# G17_Sensor_V3.net
KiCad netlist of a schematic drawn in EAGLE
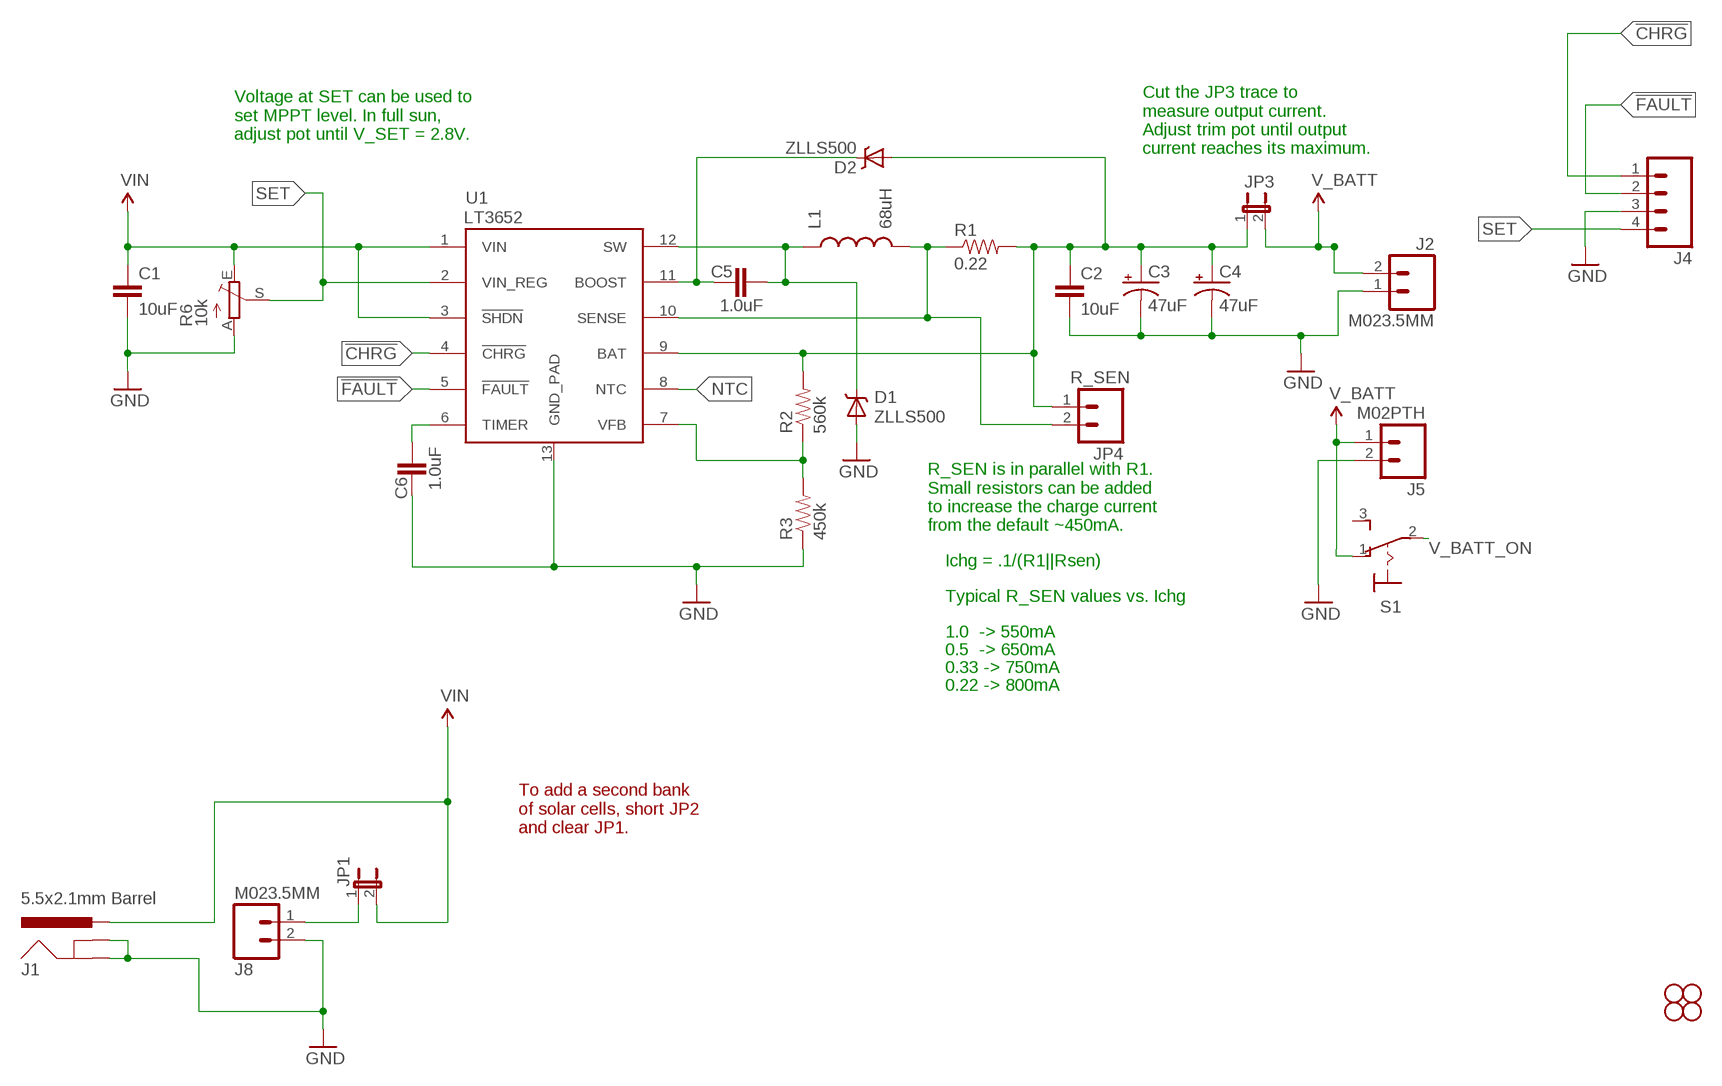
[diagram p0: schematic, sheet 1]
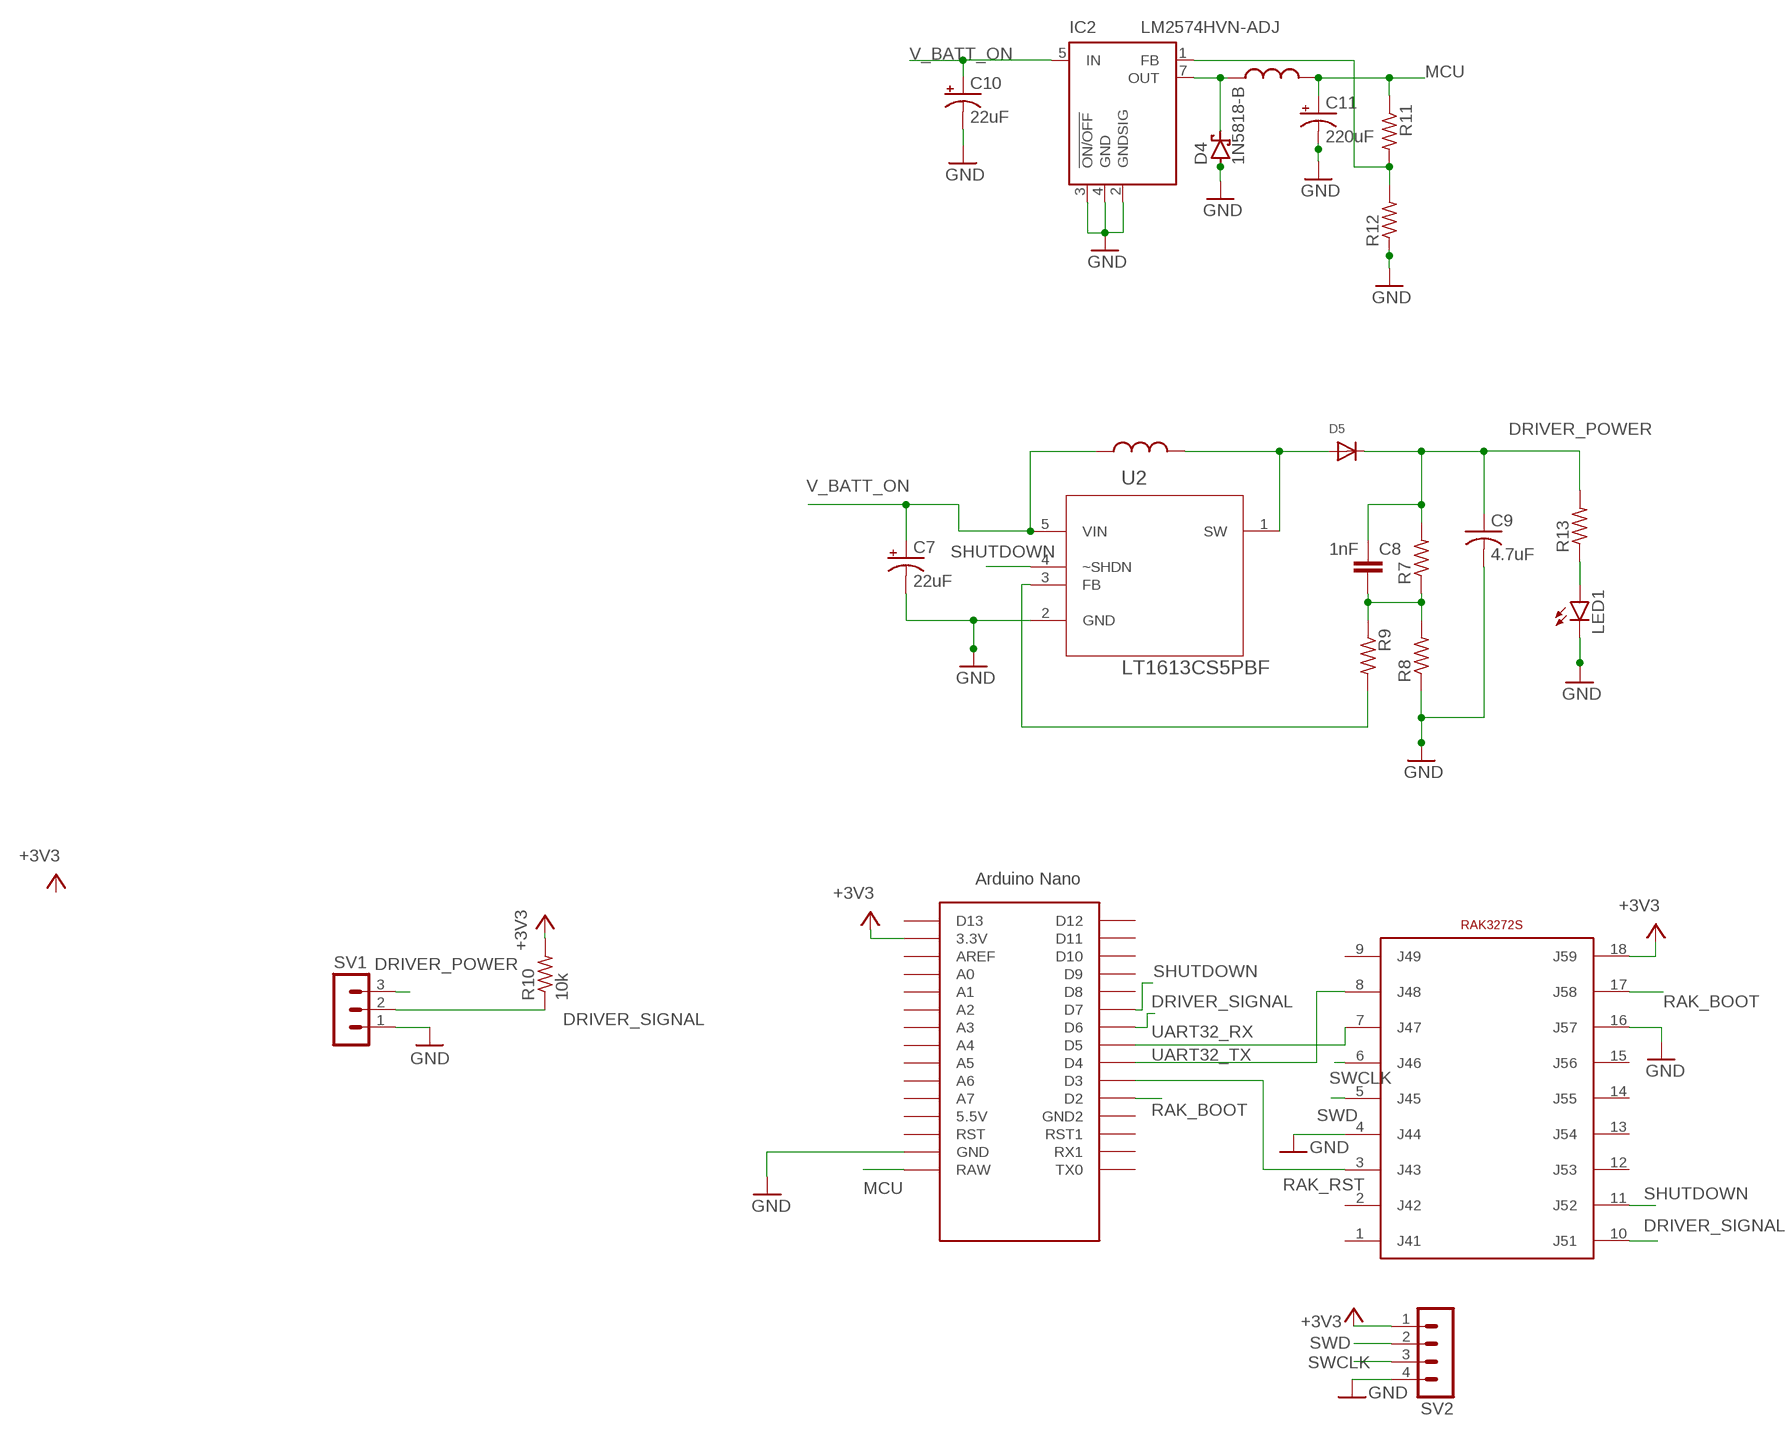
[diagram p1: schematic, sheet 2]

(export (version "E")
  (design (tool "Eeschema 10.0.6"))
  (components
    (comp (ref "C7")
      (value "22uF")
      (footprint "eagle-import:E5-6")
      (libsource (lib "eagle-import") (part "CPOL-USE5-6"))
    )
    (comp (ref "C8")
      (value "1nF")
      (footprint "eagle-import:C5B2.5")
      (libsource (lib "eagle-import") (part "C5/2.5"))
    )
    (comp (ref "C9")
      (value "4.7uF")
      (footprint "eagle-import:C025-024X044")
      (libsource (lib "eagle-import") (part "C-US025-024X044"))
    )
    (comp (ref "C10")
      (value "22uF")
      (footprint "eagle-import:E5-6")
      (libsource (lib "eagle-import") (part "CPOL-USE5-6"))
    )
    (comp (ref "C11")
      (value "220uF")
      (footprint "eagle-import:E5-6")
      (libsource (lib "eagle-import") (part "CPOL-USE5-6"))
    )
    (comp (ref "D4")
      (value "1N5818-B")
      (footprint "eagle-import:DO41-7.6")
      (libsource (lib "eagle-import") (part "1N5818-B"))
    )
    (comp (ref "D5")
      (value "DIODESOD-123")
      (footprint "eagle-import:SOD-123")
      (libsource (lib "eagle-import") (part "DIODESOD-123"))
    )
    (comp (ref "IC2")
      (value "LM2574HVN-ADJ")
      (footprint "eagle-import:DIL08")
      (libsource (lib "eagle-import") (part "LM2574?-HVNADJ"))
    )
    (comp (ref "LED1")
      (value "LED5MM")
      (footprint "eagle-import:LED5MM")
      (libsource (lib "eagle-import") (part "LED5MM"))
    )
    (comp (ref "R7")
      (value "R-US_0204/5")
      (footprint "eagle-import:0204_5")
      (libsource (lib "eagle-import") (part "R-US_0204/5"))
    )
    (comp (ref "R8")
      (value "R-US_0204/5")
      (footprint "eagle-import:0204_5")
      (libsource (lib "eagle-import") (part "R-US_0204/5"))
    )
    (comp (ref "R9")
      (value "R-US_0204/5")
      (footprint "eagle-import:0204_5")
      (libsource (lib "eagle-import") (part "R-US_0204/5"))
    )
    (comp (ref "R10")
      (value "10k")
      (footprint "eagle-import:0204_5")
      (libsource (lib "eagle-import") (part "R-US_0204/5"))
    )
    (comp (ref "R11")
      (value "R-US_0204/7")
      (footprint "eagle-import:0204_7")
      (libsource (lib "eagle-import") (part "R-US_0204/7"))
    )
    (comp (ref "R12")
      (value "R-US_0204/7")
      (footprint "eagle-import:0204_7")
      (libsource (lib "eagle-import") (part "R-US_0204/7"))
    )
    (comp (ref "R13")
      (value "R-US_0204/5")
      (footprint "eagle-import:0204_5")
      (libsource (lib "eagle-import") (part "R-US_0204/5"))
    )
    (comp (ref "SV1")
      (value "MA03-1")
      (footprint "eagle-import:MA03-1")
      (libsource (lib "eagle-import") (part "MA03-1"))
    )
    (comp (ref "SV2")
      (value "MA04-1")
      (footprint "eagle-import:MA04-1")
      (libsource (lib "eagle-import") (part "MA04-1"))
    )
    (comp (ref "U$1")
      (value "330UH_INDUCTOR")
      (footprint "eagle-import:330UH_INDUCTOR")
      (libsource (lib "eagle-import") (part "330UH_INDUCTOR"))
    )
    (comp (ref "U$2")
      (value "330UH_INDUCTOR")
      (footprint "eagle-import:330UH_INDUCTOR")
      (libsource (lib "eagle-import") (part "330UH_INDUCTOR"))
    )
    (comp (ref "U$3")
      (value "NANO")
      (footprint "eagle-import:NANO")
      (libsource (lib "eagle-import") (part "NANO"))
    )
    (comp (ref "U$4")
      (value "RAK3272S")
      (footprint "eagle-import:RAK3272SFOOTPRINT")
      (libsource (lib "eagle-import") (part "RAK3272S"))
    )
    (comp (ref "U2")
      (value "LT1613CS5PBF")
      (footprint "eagle-import:SOT95P280X145-5N")
      (fields (field (name "MPN") "LT1613CS5#PBF"))
      (libsource (lib "eagle-import") (part "LT1613CS5PBF"))
    )
    (comp (ref "C1")
      (value "10uF")
      (footprint "eagle-import:1210")
      (libsource (lib "eagle-import") (part "10UF50V20%(1210)"))
    )
    (comp (ref "C2")
      (value "10uF")
      (footprint "eagle-import:1206")
      (libsource (lib "eagle-import") (part "10UF-6.3V-20%(1206)"))
    )
    (comp (ref "C3")
      (value "47uF")
      (footprint "eagle-import:EIA3528")
      (libsource (lib "eagle-import") (part "47UF-TANT"))
    )
    (comp (ref "C4")
      (value "47uF")
      (footprint "eagle-import:EIA3528")
      (libsource (lib "eagle-import") (part "47UF-TANT"))
    )
    (comp (ref "C5")
      (value "1.0uF")
      (footprint "eagle-import:0603-CAP")
      (libsource (lib "eagle-import") (part "1.0UF-16V-10%(0603)"))
    )
    (comp (ref "C6")
      (value "1.0uF")
      (footprint "eagle-import:0603-CAP")
      (libsource (lib "eagle-import") (part "1.0UF-16V-10%(0603)"))
    )
    (comp (ref "D1")
      (value "ZLLS500")
      (footprint "eagle-import:SOT23")
      (libsource (lib "eagle-import") (part "ZLLS500ZLLS500"))
    )
    (comp (ref "D2")
      (value "ZLLS500")
      (footprint "eagle-import:SOT23")
      (libsource (lib "eagle-import") (part "ZLLS500ZLLS500"))
    )
    (comp (ref "J1")
      (value "5.5x2.1mm Barrel")
      (footprint "eagle-import:POWER_JACK_SMD")
      (libsource (lib "eagle-import") (part "POWER_JACKSMD"))
    )
    (comp (ref "J2")
      (value "M023.5MM")
      (footprint "eagle-import:SCREWTERMINAL-3.5MM-2")
      (libsource (lib "eagle-import") (part "M023.5MM"))
    )
    (comp (ref "J4")
      (value "M04PTH")
      (footprint "eagle-import:1X04")
      (libsource (lib "eagle-import") (part "M04PTH"))
    )
    (comp (ref "J5")
      (value "M02PTH")
      (footprint "eagle-import:1X02")
      (libsource (lib "eagle-import") (part "M02PTH"))
    )
    (comp (ref "J8")
      (value "M023.5MM")
      (footprint "eagle-import:SCREWTERMINAL-3.5MM-2")
      (libsource (lib "eagle-import") (part "M023.5MM"))
    )
    (comp (ref "JP1")
      (value "JUMPER-2SMD-NC")
      (footprint "eagle-import:SJ_2S")
      (libsource (lib "eagle-import") (part "JUMPER-2SMD-NC"))
    )
    (comp (ref "JP3")
      (value "JUMPER-PTH-2-NC")
      (footprint "eagle-import:PTH-JUMPER-NC_BOTTOM_NO_SILK")
      (libsource (lib "eagle-import") (part "JUMPER-PTH-2-NC"))
    )
    (comp (ref "JP4")
      (value "R_SEN")
      (footprint "eagle-import:1X02")
      (libsource (lib "eagle-import") (part "M02PTH"))
    )
    (comp (ref "L1")
      (value "68uH")
      (footprint "eagle-import:CR75")
      (libsource (lib "eagle-import") (part "INDUCTOR68UH-1A"))
    )
    (comp (ref "R1")
      (value "0.22")
      (footprint "eagle-import:0805")
      (libsource (lib "eagle-import") (part "0.22OHM1/4W1%(0805)"))
    )
    (comp (ref "R2")
      (value "560k")
      (footprint "eagle-import:0603-RES")
      (libsource (lib "eagle-import") (part "47KOHM1/10W1%(0603)"))
    )
    (comp (ref "R3")
      (value "450k")
      (footprint "eagle-import:0603-RES")
      (libsource (lib "eagle-import") (part "220KOHM1/10W1%(0603)"))
    )
    (comp (ref "R6")
      (value "10k")
      (footprint "eagle-import:S63S")
      (libsource (lib "eagle-import") (part "TRIM_EU-S63S"))
    )
    (comp (ref "S1")
      (value "M9040P")
      (footprint "eagle-import:M9040P")
      (libsource (lib "eagle-import") (part "M9040P"))
    )
    (comp (ref "STANDOFF1")
      (value "STAND-OFF")
      (footprint "eagle-import:STAND-OFF")
      (libsource (lib "eagle-import") (part "STAND-OFF"))
    )
    (comp (ref "STANDOFF2")
      (value "STAND-OFF")
      (footprint "eagle-import:STAND-OFF")
      (libsource (lib "eagle-import") (part "STAND-OFF"))
    )
    (comp (ref "STANDOFF3")
      (value "STAND-OFF")
      (footprint "eagle-import:STAND-OFF")
      (libsource (lib "eagle-import") (part "STAND-OFF"))
    )
    (comp (ref "STANDOFF4")
      (value "STAND-OFF")
      (footprint "eagle-import:STAND-OFF")
      (libsource (lib "eagle-import") (part "STAND-OFF"))
    )
    (comp (ref "U1")
      (value "LT3652")
      (footprint "eagle-import:MSOP-12_GND")
      (libsource (lib "eagle-import") (part "LT3652"))
    )
  )
  (nets
    (net (code "1") (name "+3V3") (class "Default")
      (node (ref "R10") (pin "2") (pinfunction "2_2") (pintype "passive"))
      (node (ref "SV2") (pin "1") (pinfunction "1_1") (pintype "passive"))
      (node (ref "U$3") (pin "3.3V") (pinfunction "3.3V_3.3V") (pintype "bidirectional"))
      (node (ref "U$4") (pin "18") (pinfunction "J59_18") (pintype "bidirectional"))
    )
    (net (code "2") (name "DRIVER_POWER") (class "Default")
      (node (ref "C8") (pin "1") (pinfunction "1_1") (pintype "passive"))
      (node (ref "C9") (pin "1") (pinfunction "1_1") (pintype "passive"))
      (node (ref "D5") (pin "C") (pinfunction "C_C") (pintype "passive"))
      (node (ref "R13") (pin "2") (pinfunction "2_2") (pintype "passive"))
      (node (ref "R7") (pin "2") (pinfunction "2_2") (pintype "passive"))
      (node (ref "SV1") (pin "3") (pinfunction "3_3") (pintype "passive"))
    )
    (net (code "3") (name "DRIVER_SIGNAL") (class "Default")
      (node (ref "R10") (pin "1") (pinfunction "1_1") (pintype "passive"))
      (node (ref "SV1") (pin "2") (pinfunction "2_2") (pintype "passive"))
      (node (ref "U$3") (pin "D6") (pinfunction "D6_D6") (pintype "bidirectional"))
      (node (ref "U$4") (pin "10") (pinfunction "J51_10") (pintype "bidirectional"))
    )
    (net (code "4") (name "GND") (class "Default")
      (node (ref "C1") (pin "2") (pinfunction "2_2") (pintype "passive"))
      (node (ref "C10") (pin "-") (pinfunction "-_-") (pintype "passive"))
      (node (ref "C11") (pin "-") (pinfunction "-_-") (pintype "passive"))
      (node (ref "C2") (pin "2") (pinfunction "2_2") (pintype "passive"))
      (node (ref "C3") (pin "C") (pinfunction "-_C") (pintype "passive"))
      (node (ref "C4") (pin "C") (pinfunction "-_C") (pintype "passive"))
      (node (ref "C6") (pin "1") (pinfunction "1_1") (pintype "passive"))
      (node (ref "C7") (pin "-") (pinfunction "-_-") (pintype "passive"))
      (node (ref "C9") (pin "2") (pinfunction "2_2") (pintype "passive"))
      (node (ref "D1") (pin "1") (pinfunction "A_1") (pintype "passive"))
      (node (ref "D4") (pin "A") (pinfunction "A_A") (pintype "passive"))
      (node (ref "IC2") (pin "2") (pinfunction "GNDSIG_2") (pintype "input"))
      (node (ref "IC2") (pin "3") (pinfunction "~{ON/OFF}_3") (pintype "input"))
      (node (ref "IC2") (pin "4") (pinfunction "GND_4") (pintype "power_in"))
      (node (ref "J1") (pin "GND") (pinfunction "GNDBREAK_GND") (pintype "bidirectional"))
      (node (ref "J1") (pin "P$4") (pinfunction "GND_P$4") (pintype "bidirectional"))
      (node (ref "J2") (pin "1") (pinfunction "1_1") (pintype "passive"))
      (node (ref "J4") (pin "3") (pinfunction "3_3") (pintype "passive"))
      (node (ref "J5") (pin "2") (pinfunction "2_2") (pintype "passive"))
      (node (ref "J8") (pin "2") (pinfunction "2_2") (pintype "passive"))
      (node (ref "LED1") (pin "K") (pinfunction "C_K") (pintype "passive"))
      (node (ref "R12") (pin "1") (pinfunction "1_1") (pintype "passive"))
      (node (ref "R3") (pin "1") (pinfunction "1_1") (pintype "passive"))
      (node (ref "R6") (pin "A") (pinfunction "A_A") (pintype "passive"))
      (node (ref "R8") (pin "1") (pinfunction "1_1") (pintype "passive"))
      (node (ref "SV1") (pin "1") (pinfunction "1_1") (pintype "passive"))
      (node (ref "SV2") (pin "4") (pinfunction "4_4") (pintype "passive"))
      (node (ref "U$3") (pin "GND") (pinfunction "GND_GND") (pintype "bidirectional"))
      (node (ref "U$4") (pin "16") (pinfunction "J57_16") (pintype "bidirectional"))
      (node (ref "U$4") (pin "4") (pinfunction "J44_4") (pintype "bidirectional"))
      (node (ref "U1") (pin "13") (pinfunction "GND_PAD_13") (pintype "bidirectional"))
      (node (ref "U2") (pin "2") (pinfunction "GND_2") (pintype "passive"))
    )
    (net (code "5") (name "MCU") (class "Default")
      (node (ref "C11") (pin "+") (pinfunction "+_+") (pintype "passive"))
      (node (ref "R11") (pin "1") (pinfunction "1_1") (pintype "passive"))
      (node (ref "U$1") (pin "P$2") (pinfunction "P$2_P$2") (pintype "bidirectional"))
      (node (ref "U$3") (pin "RAW") (pinfunction "RAW_RAW") (pintype "bidirectional"))
    )
    (net (code "6") (name "NTC") (class "Default")
      (node (ref "U1") (pin "8") (pinfunction "NTC_8") (pintype "bidirectional"))
    )
    (net (code "7") (name "Net-(C3-+)") (class "Default")
      (node (ref "C2") (pin "1") (pinfunction "1_1") (pintype "passive"))
      (node (ref "C3") (pin "A") (pinfunction "+_A") (pintype "passive"))
      (node (ref "C4") (pin "A") (pinfunction "+_A") (pintype "passive"))
      (node (ref "D2") (pin "1") (pinfunction "A_1") (pintype "passive"))
      (node (ref "JP3") (pin "1") (pinfunction "1_1") (pintype "passive"))
      (node (ref "JP4") (pin "1") (pinfunction "1_1") (pintype "passive"))
      (node (ref "R1") (pin "2") (pinfunction "2_2") (pintype "passive"))
      (node (ref "R2") (pin "2") (pinfunction "2_2") (pintype "passive"))
      (node (ref "U1") (pin "9") (pinfunction "BAT_9") (pintype "bidirectional"))
    )
    (net (code "8") (name "Net-(C8-Pad2)") (class "Default")
      (node (ref "C8") (pin "2") (pinfunction "2_2") (pintype "passive"))
      (node (ref "R7") (pin "1") (pinfunction "1_1") (pintype "passive"))
      (node (ref "R8") (pin "2") (pinfunction "2_2") (pintype "passive"))
      (node (ref "R9") (pin "1") (pinfunction "1_1") (pintype "passive"))
    )
    (net (code "9") (name "Net-(D1-C)") (class "Default")
      (node (ref "C5") (pin "2") (pinfunction "2_2") (pintype "passive"))
      (node (ref "D1") (pin "3") (pinfunction "C_3") (pintype "passive"))
      (node (ref "L1") (pin "P$1") (pinfunction "1_P$1") (pintype "passive"))
      (node (ref "U1") (pin "12") (pinfunction "SW_12") (pintype "bidirectional"))
    )
    (net (code "10") (name "Net-(D2-C)") (class "Default")
      (node (ref "C5") (pin "1") (pinfunction "1_1") (pintype "passive"))
      (node (ref "D2") (pin "3") (pinfunction "C_3") (pintype "passive"))
      (node (ref "U1") (pin "11") (pinfunction "BOOST_11") (pintype "bidirectional"))
    )
    (net (code "11") (name "Net-(IC2-FB)") (class "Default")
      (node (ref "IC2") (pin "1") (pinfunction "FB_1") (pintype "input"))
      (node (ref "R11") (pin "2") (pinfunction "2_2") (pintype "passive"))
      (node (ref "R12") (pin "2") (pinfunction "2_2") (pintype "passive"))
    )
    (net (code "12") (name "Net-(IC2-OUT)") (class "Default")
      (node (ref "D4") (pin "C") (pinfunction "C_C") (pintype "passive"))
      (node (ref "IC2") (pin "7") (pinfunction "OUT_7") (pintype "passive"))
      (node (ref "U$1") (pin "P$1") (pinfunction "P$1_P$1") (pintype "bidirectional"))
    )
    (net (code "13") (name "Net-(J8-Pad1)") (class "Default")
      (node (ref "J8") (pin "1") (pinfunction "1_1") (pintype "passive"))
      (node (ref "JP1") (pin "1") (pinfunction "1_1") (pintype "passive"))
    )
    (net (code "14") (name "Net-(L1-2)") (class "Default")
      (node (ref "JP4") (pin "2") (pinfunction "2_2") (pintype "passive"))
      (node (ref "L1") (pin "P$2") (pinfunction "2_P$2") (pintype "passive"))
      (node (ref "R1") (pin "1") (pinfunction "1_1") (pintype "passive"))
      (node (ref "U1") (pin "10") (pinfunction "SENSE_10") (pintype "bidirectional"))
    )
    (net (code "15") (name "Net-(LED1-PadA)") (class "Default")
      (node (ref "LED1") (pin "A") (pinfunction "A_A") (pintype "passive"))
      (node (ref "R13") (pin "1") (pinfunction "1_1") (pintype "passive"))
    )
    (net (code "16") (name "Net-(U1-TIMER)") (class "Default")
      (node (ref "C6") (pin "2") (pinfunction "2_2") (pintype "passive"))
      (node (ref "U1") (pin "6") (pinfunction "TIMER_6") (pintype "bidirectional"))
    )
    (net (code "17") (name "Net-(U1-VFB)") (class "Default")
      (node (ref "R2") (pin "1") (pinfunction "1_1") (pintype "passive"))
      (node (ref "R3") (pin "2") (pinfunction "2_2") (pintype "passive"))
      (node (ref "U1") (pin "7") (pinfunction "VFB_7") (pintype "bidirectional"))
    )
    (net (code "18") (name "Net-(U2-FB)") (class "Default")
      (node (ref "R9") (pin "2") (pinfunction "2_2") (pintype "passive"))
      (node (ref "U2") (pin "3") (pinfunction "FB_3") (pintype "input"))
    )
    (net (code "19") (name "Net-(U2-SW)") (class "Default")
      (node (ref "D5") (pin "A") (pinfunction "A_A") (pintype "passive"))
      (node (ref "U$2") (pin "P$2") (pinfunction "P$2_P$2") (pintype "bidirectional"))
      (node (ref "U2") (pin "1") (pinfunction "SW_1") (pintype "output"))
    )
    (net (code "20") (name "RAK_BOOT") (class "Default")
      (node (ref "U$3") (pin "D2") (pinfunction "D2_D2") (pintype "bidirectional"))
      (node (ref "U$4") (pin "17") (pinfunction "J58_17") (pintype "bidirectional"))
    )
    (net (code "21") (name "RAK_RST") (class "Default")
      (node (ref "U$3") (pin "D3") (pinfunction "D3_D3") (pintype "bidirectional"))
      (node (ref "U$4") (pin "3") (pinfunction "J43_3") (pintype "bidirectional"))
    )
    (net (code "22") (name "SET") (class "Default")
      (node (ref "J4") (pin "4") (pinfunction "4_4") (pintype "passive"))
      (node (ref "R6") (pin "S") (pinfunction "S_S") (pintype "passive"))
      (node (ref "U1") (pin "2") (pinfunction "VIN_REG_2") (pintype "bidirectional"))
    )
    (net (code "23") (name "SHUTDOWN") (class "Default")
      (node (ref "U$3") (pin "D7") (pinfunction "D7_D7") (pintype "bidirectional"))
      (node (ref "U$4") (pin "11") (pinfunction "J52_11") (pintype "bidirectional"))
      (node (ref "U2") (pin "4") (pinfunction "~{SHDN}_4") (pintype "input"))
    )
    (net (code "24") (name "SWCLK") (class "Default")
      (node (ref "SV2") (pin "3") (pinfunction "3_3") (pintype "passive"))
      (node (ref "U$4") (pin "6") (pinfunction "J46_6") (pintype "bidirectional"))
    )
    (net (code "25") (name "SWD") (class "Default")
      (node (ref "SV2") (pin "2") (pinfunction "2_2") (pintype "passive"))
      (node (ref "U$4") (pin "5") (pinfunction "J45_5") (pintype "bidirectional"))
    )
    (net (code "26") (name "UART32_RX") (class "Default")
      (node (ref "U$3") (pin "D5") (pinfunction "D5_D5") (pintype "bidirectional"))
      (node (ref "U$4") (pin "7") (pinfunction "J47_7") (pintype "bidirectional"))
    )
    (net (code "27") (name "UART32_TX") (class "Default")
      (node (ref "U$3") (pin "D4") (pinfunction "D4_D4") (pintype "bidirectional"))
      (node (ref "U$4") (pin "8") (pinfunction "J48_8") (pintype "bidirectional"))
    )
    (net (code "28") (name "VIN") (class "Default")
      (node (ref "C1") (pin "1") (pinfunction "1_1") (pintype "passive"))
      (node (ref "J1") (pin "VIN0") (pinfunction "PWR_VIN0") (pintype "bidirectional"))
      (node (ref "JP1") (pin "2") (pinfunction "2_2") (pintype "passive"))
      (node (ref "R6") (pin "E") (pinfunction "E_E") (pintype "passive"))
      (node (ref "U1") (pin "1") (pinfunction "VIN_1") (pintype "bidirectional"))
      (node (ref "U1") (pin "3") (pinfunction "~{SHDN}_3") (pintype "bidirectional"))
    )
    (net (code "29") (name "V_BATT") (class "Default")
      (node (ref "J2") (pin "2") (pinfunction "2_2") (pintype "passive"))
      (node (ref "J5") (pin "1") (pinfunction "1_1") (pintype "passive"))
      (node (ref "JP3") (pin "2") (pinfunction "2_2") (pintype "passive"))
      (node (ref "S1") (pin "1") (pinfunction "O_1") (pintype "passive"))
    )
    (net (code "30") (name "V_BATT_ON") (class "Default")
      (node (ref "C10") (pin "+") (pinfunction "+_+") (pintype "passive"))
      (node (ref "C7") (pin "+") (pinfunction "+_+") (pintype "passive"))
      (node (ref "IC2") (pin "5") (pinfunction "IN_5") (pintype "input"))
      (node (ref "S1") (pin "2") (pinfunction "P_2") (pintype "passive"))
      (node (ref "U$2") (pin "P$1") (pinfunction "P$1_P$1") (pintype "bidirectional"))
      (node (ref "U2") (pin "5") (pinfunction "VIN_5") (pintype "power_in"))
    )
    (net (code "31") (name "unconnected-(S1-S-Pad3)") (class "Default")
      (node (ref "S1") (pin "3") (pinfunction "S_3") (pintype "passive"))
    )
    (net (code "32") (name "unconnected-(U$3-5.5V-Pad5V)") (class "Default")
      (node (ref "U$3") (pin "5V") (pinfunction "5.5V_5V") (pintype "bidirectional"))
    )
    (net (code "33") (name "unconnected-(U$3-GND2-PadGND1)") (class "Default")
      (node (ref "U$3") (pin "GND1") (pinfunction "GND2_GND1") (pintype "bidirectional"))
    )
    (net (code "34") (name "unconnected-(U$3-PadA0)") (class "Default")
      (node (ref "U$3") (pin "A0") (pinfunction "A0_A0") (pintype "bidirectional"))
    )
    (net (code "35") (name "unconnected-(U$3-PadA1)") (class "Default")
      (node (ref "U$3") (pin "A1") (pinfunction "A1_A1") (pintype "bidirectional"))
    )
    (net (code "36") (name "unconnected-(U$3-PadA2)") (class "Default")
      (node (ref "U$3") (pin "A2") (pinfunction "A2_A2") (pintype "bidirectional"))
    )
    (net (code "37") (name "unconnected-(U$3-PadA3)") (class "Default")
      (node (ref "U$3") (pin "A3") (pinfunction "A3_A3") (pintype "bidirectional"))
    )
    (net (code "38") (name "unconnected-(U$3-PadA4)") (class "Default")
      (node (ref "U$3") (pin "A4") (pinfunction "A4_A4") (pintype "bidirectional"))
    )
    (net (code "39") (name "unconnected-(U$3-PadA5)") (class "Default")
      (node (ref "U$3") (pin "A5") (pinfunction "A5_A5") (pintype "bidirectional"))
    )
    (net (code "40") (name "unconnected-(U$3-PadA6)") (class "Default")
      (node (ref "U$3") (pin "A6") (pinfunction "A6_A6") (pintype "bidirectional"))
    )
    (net (code "41") (name "unconnected-(U$3-PadA7)") (class "Default")
      (node (ref "U$3") (pin "A7") (pinfunction "A7_A7") (pintype "bidirectional"))
    )
    (net (code "42") (name "unconnected-(U$3-PadAREF)") (class "Default")
      (node (ref "U$3") (pin "AREF") (pinfunction "AREF_AREF") (pintype "bidirectional"))
    )
    (net (code "43") (name "unconnected-(U$3-PadD8)") (class "Default")
      (node (ref "U$3") (pin "D8") (pinfunction "D8_D8") (pintype "bidirectional"))
    )
    (net (code "44") (name "unconnected-(U$3-PadD9)") (class "Default")
      (node (ref "U$3") (pin "D9") (pinfunction "D9_D9") (pintype "bidirectional"))
    )
    (net (code "45") (name "unconnected-(U$3-PadD10)") (class "Default")
      (node (ref "U$3") (pin "D10") (pinfunction "D10_D10") (pintype "bidirectional"))
    )
    (net (code "46") (name "unconnected-(U$3-PadD11)") (class "Default")
      (node (ref "U$3") (pin "D11") (pinfunction "D11_D11") (pintype "bidirectional"))
    )
    (net (code "47") (name "unconnected-(U$3-PadD12)") (class "Default")
      (node (ref "U$3") (pin "D12") (pinfunction "D12_D12") (pintype "bidirectional"))
    )
    (net (code "48") (name "unconnected-(U$3-PadD13)") (class "Default")
      (node (ref "U$3") (pin "D13") (pinfunction "D13_D13") (pintype "bidirectional"))
    )
    (net (code "49") (name "unconnected-(U$3-PadICSP1)") (class "Default")
      (node (ref "U$3") (pin "ICSP1") (pinfunction "ICSP1_ICSP1") (pintype "bidirectional"))
    )
    (net (code "50") (name "unconnected-(U$3-PadICSP2)") (class "Default")
      (node (ref "U$3") (pin "ICSP2") (pinfunction "ICSP2_ICSP2") (pintype "bidirectional"))
    )
    (net (code "51") (name "unconnected-(U$3-PadICSP3)") (class "Default")
      (node (ref "U$3") (pin "ICSP3") (pinfunction "ICSP3_ICSP3") (pintype "bidirectional"))
    )
    (net (code "52") (name "unconnected-(U$3-PadICSP4)") (class "Default")
      (node (ref "U$3") (pin "ICSP4") (pinfunction "ICSP4_ICSP4") (pintype "bidirectional"))
    )
    (net (code "53") (name "unconnected-(U$3-PadICSP5)") (class "Default")
      (node (ref "U$3") (pin "ICSP5") (pinfunction "ICSP5_ICSP5") (pintype "bidirectional"))
    )
    (net (code "54") (name "unconnected-(U$3-PadICSP6)") (class "Default")
      (node (ref "U$3") (pin "ICSP6") (pinfunction "ICSP6_ICSP6") (pintype "bidirectional"))
    )
    (net (code "55") (name "unconnected-(U$3-PadRST)") (class "Default")
      (node (ref "U$3") (pin "RST") (pinfunction "RST_RST") (pintype "bidirectional"))
    )
    (net (code "56") (name "unconnected-(U$3-PadRST1)") (class "Default")
      (node (ref "U$3") (pin "RST1") (pinfunction "RST1_RST1") (pintype "bidirectional"))
    )
    (net (code "57") (name "unconnected-(U$3-PadRX1)") (class "Default")
      (node (ref "U$3") (pin "RX1") (pinfunction "RX1_RX1") (pintype "bidirectional"))
    )
    (net (code "58") (name "unconnected-(U$3-PadTX0)") (class "Default")
      (node (ref "U$3") (pin "TX0") (pinfunction "TX0_TX0") (pintype "bidirectional"))
    )
    (net (code "59") (name "unconnected-(U$4-J41-Pad1)") (class "Default")
      (node (ref "U$4") (pin "1") (pinfunction "J41_1") (pintype "bidirectional"))
    )
    (net (code "60") (name "unconnected-(U$4-J42-Pad2)") (class "Default")
      (node (ref "U$4") (pin "2") (pinfunction "J42_2") (pintype "bidirectional"))
    )
    (net (code "61") (name "unconnected-(U$4-J49-Pad9)") (class "Default")
      (node (ref "U$4") (pin "9") (pinfunction "J49_9") (pintype "bidirectional"))
    )
    (net (code "62") (name "unconnected-(U$4-J53-Pad12)") (class "Default")
      (node (ref "U$4") (pin "12") (pinfunction "J53_12") (pintype "bidirectional"))
    )
    (net (code "63") (name "unconnected-(U$4-J54-Pad13)") (class "Default")
      (node (ref "U$4") (pin "13") (pinfunction "J54_13") (pintype "bidirectional"))
    )
    (net (code "64") (name "unconnected-(U$4-J55-Pad14)") (class "Default")
      (node (ref "U$4") (pin "14") (pinfunction "J55_14") (pintype "bidirectional"))
    )
    (net (code "65") (name "unconnected-(U$4-J56-Pad15)") (class "Default")
      (node (ref "U$4") (pin "15") (pinfunction "J56_15") (pintype "bidirectional"))
    )
    (net (code "66") (name "~{CHRG}") (class "Default")
      (node (ref "J4") (pin "1") (pinfunction "1_1") (pintype "passive"))
      (node (ref "U1") (pin "4") (pinfunction "~{CHRG}_4") (pintype "bidirectional"))
    )
    (net (code "67") (name "~{FAULT}") (class "Default")
      (node (ref "J4") (pin "2") (pinfunction "2_2") (pintype "passive"))
      (node (ref "U1") (pin "5") (pinfunction "~{FAULT}_5") (pintype "bidirectional"))
    )
  )
)
